# 3_mcu.net
KiCad netlist of a schematic drawn in Altium Designer
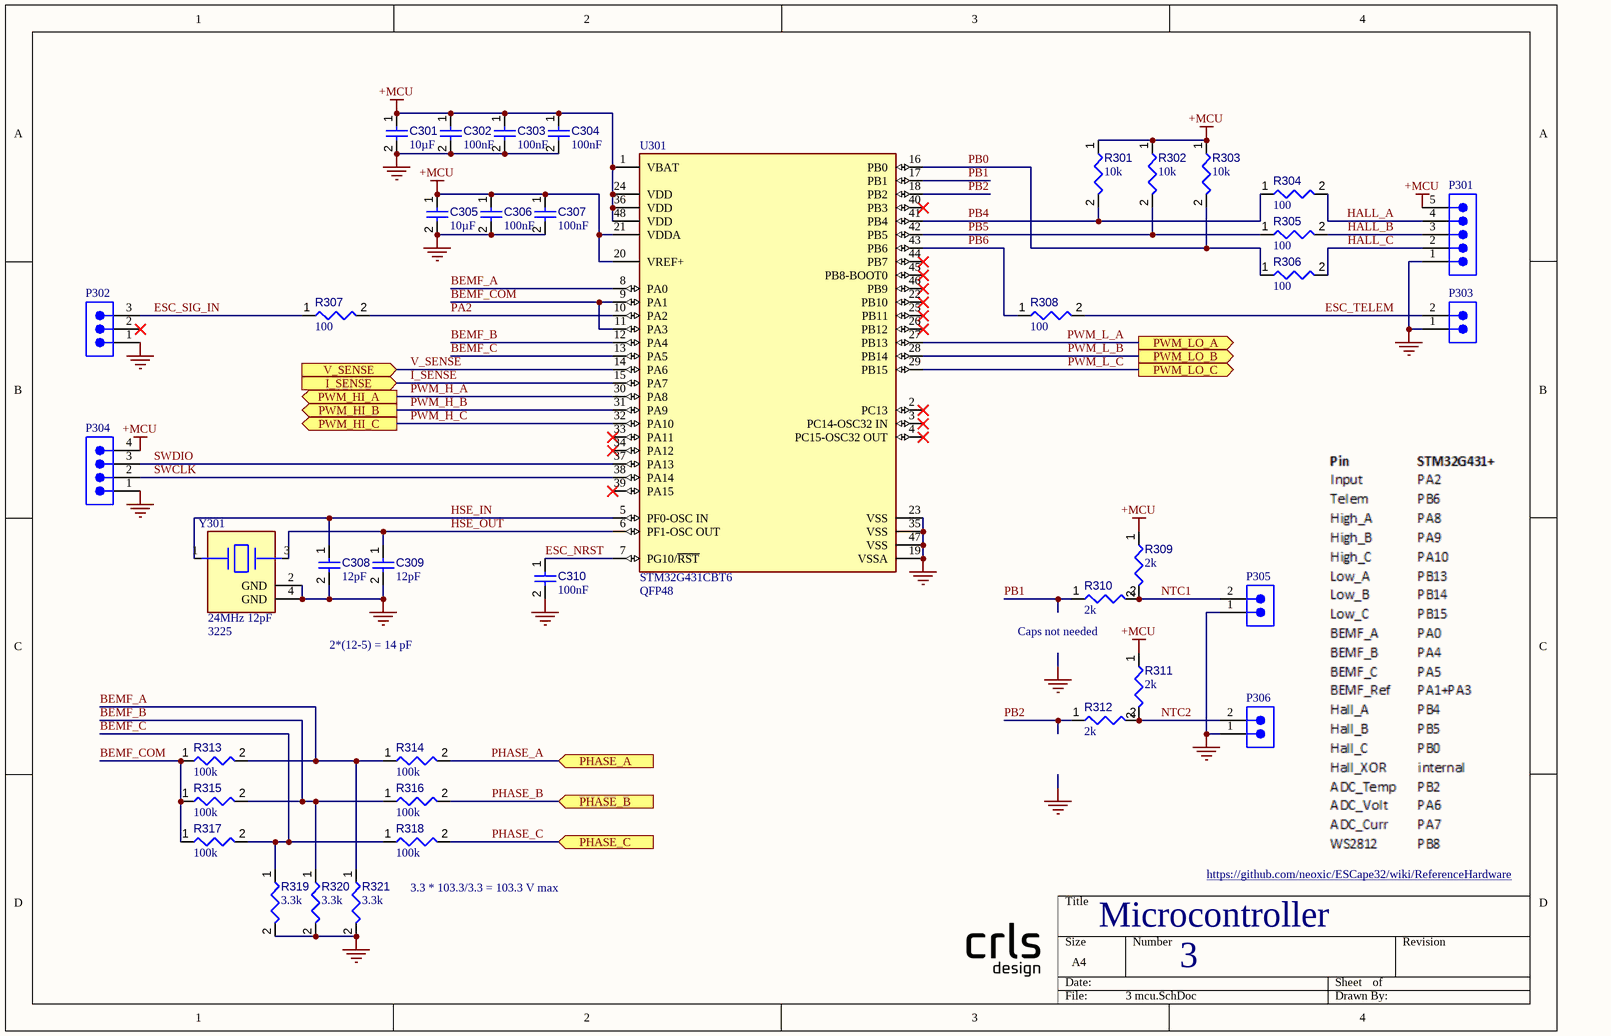
[diagram p0: 3 mcu.SchDoc]

(export (version "E")
  (design (tool "Eeschema 10.0.6"))
  (components
    (comp (ref "C301")
      (value "10µF")
      (footprint "CAPC0603(1608)100_L")
      (description "Chip Capacitor, 10µF +/-20%, 10V, 0603, Thickness 1 mm")
      (fields (field (name "TOLERANCE") "10%") (field (name "Comment") "Capacitor 10µF +/-20% 10V 0603"))
      (libsource (lib "UBC Uncrewed Aircraft Systems") (part "CAP-NP-2"))
    )
    (comp (ref "C302")
      (value "100nF")
      (footprint "CAPC0402(1005)60_L")
      (description "Chip Capacitor, 100nF +/-20%, 25V, 0402, Thickness 0.6 mm")
      (fields (field (name "TOLERANCE") "10%") (field (name "Comment") "Capacitor 100nF +/-20% 25V 0402"))
      (libsource (lib "UBC Uncrewed Aircraft Systems") (part "CAP-NP-2"))
    )
    (comp (ref "C303")
      (value "100nF")
      (footprint "CAPC0402(1005)60_L")
      (description "Chip Capacitor, 100nF +/-20%, 25V, 0402, Thickness 0.6 mm")
      (fields (field (name "TOLERANCE") "10%") (field (name "Comment") "Capacitor 100nF +/-20% 25V 0402"))
      (libsource (lib "UBC Uncrewed Aircraft Systems") (part "CAP-NP-2"))
    )
    (comp (ref "C304")
      (value "100nF")
      (footprint "CAPC0402(1005)60_L")
      (description "Chip Capacitor, 100nF +/-20%, 25V, 0402, Thickness 0.6 mm")
      (fields (field (name "TOLERANCE") "10%") (field (name "Comment") "Capacitor 100nF +/-20% 25V 0402"))
      (libsource (lib "UBC Uncrewed Aircraft Systems") (part "CAP-NP-2"))
    )
    (comp (ref "C305")
      (value "10µF")
      (footprint "CAPC0603(1608)100_L")
      (description "Chip Capacitor, 10µF +/-20%, 10V, 0603, Thickness 1 mm")
      (fields (field (name "TOLERANCE") "10%") (field (name "Comment") "Capacitor 10µF +/-20% 10V 0603"))
      (libsource (lib "UBC Uncrewed Aircraft Systems") (part "CAP-NP-2"))
    )
    (comp (ref "C306")
      (value "100nF")
      (footprint "CAPC0402(1005)60_L")
      (description "Chip Capacitor, 100nF +/-20%, 25V, 0402, Thickness 0.6 mm")
      (fields (field (name "TOLERANCE") "10%") (field (name "Comment") "Capacitor 100nF +/-20% 25V 0402"))
      (libsource (lib "UBC Uncrewed Aircraft Systems") (part "CAP-NP-2"))
    )
    (comp (ref "C307")
      (value "100nF")
      (footprint "CAPC0402(1005)60_L")
      (description "Chip Capacitor, 100nF +/-20%, 25V, 0402, Thickness 0.6 mm")
      (fields (field (name "TOLERANCE") "10%") (field (name "Comment") "Capacitor 100nF +/-20% 25V 0402"))
      (libsource (lib "UBC Uncrewed Aircraft Systems") (part "CAP-NP-2"))
    )
    (comp (ref "C308")
      (value "12pF")
      (footprint "CAPC0402(1005)33_L")
      (description "Chip Capacitor, 12pF +/-10%, 50V, 0402, Thickness 0.33 mm")
      (fields (field (name "TOLERANCE") "20%") (field (name "Comment") "Capacitor 12pF +/-10% 50V 0402"))
      (libsource (lib "UBC Uncrewed Aircraft Systems") (part "CAP-NP-2"))
    )
    (comp (ref "C309")
      (value "12pF")
      (footprint "CAPC0402(1005)33_L")
      (description "Chip Capacitor, 12pF +/-10%, 50V, 0402, Thickness 0.33 mm")
      (fields (field (name "TOLERANCE") "20%") (field (name "Comment") "Capacitor 12pF +/-10% 50V 0402"))
      (libsource (lib "UBC Uncrewed Aircraft Systems") (part "CAP-NP-2"))
    )
    (comp (ref "C310")
      (value "100nF")
      (footprint "CAPC0402(1005)60_L")
      (description "Chip Capacitor, 100nF +/-20%, 25V, 0402, Thickness 0.6 mm")
      (fields (field (name "TOLERANCE") "10%") (field (name "Comment") "Capacitor 100nF +/-20% 25V 0402"))
      (libsource (lib "UBC Uncrewed Aircraft Systems") (part "CAP-NP-2"))
    )
    (comp (ref "P301")
      (value "61300511121")
      (footprint "61300511121")
      (libsource (lib "Altium Content Vault") (part "Header_Male_1R_05P"))
    )
    (comp (ref "P302")
      (value "62000311121")
      (footprint "62000311121")
      (libsource (lib "Altium Content Vault") (part "Header_Male_1R_03P"))
    )
    (comp (ref "P303")
      (value "62000211121")
      (footprint "62000211121")
      (libsource (lib "Altium Content Vault") (part "Header_Male_1R_02P"))
    )
    (comp (ref "P304")
      (value "61300411121")
      (footprint "61300411121")
      (libsource (lib "Altium Content Vault") (part "Header_Male_1R_04P"))
    )
    (comp (ref "P305")
      (value "62000211121")
      (footprint "62000211121")
      (libsource (lib "Altium Content Vault") (part "Header_Male_1R_02P"))
    )
    (comp (ref "P306")
      (value "62000211121")
      (footprint "62000211121")
      (libsource (lib "Altium Content Vault") (part "Header_Male_1R_02P"))
    )
    (comp (ref "R301")
      (value "10k")
      (footprint "RESC0402(1005)_L")
      (description "Chip Resistor, 10 kOhms, +/-1 %, 63 mW, -55 to 125 degC, 0402")
      (fields (field (name "POWER") "63mW") (field (name "TOLERANCE") "1%"))
      (libsource (lib "UBC Uncrewed Aircraft Systems") (part "RES-2"))
    )
    (comp (ref "R302")
      (value "10k")
      (footprint "RESC0402(1005)_L")
      (description "Chip Resistor, 10 kOhms, +/-1 %, 63 mW, -55 to 125 degC, 0402")
      (fields (field (name "POWER") "63mW") (field (name "TOLERANCE") "1%"))
      (libsource (lib "UBC Uncrewed Aircraft Systems") (part "RES-2"))
    )
    (comp (ref "R303")
      (value "10k")
      (footprint "RESC0402(1005)_L")
      (description "Chip Resistor, 10 kOhms, +/-1 %, 63 mW, -55 to 125 degC, 0402")
      (fields (field (name "POWER") "63mW") (field (name "TOLERANCE") "1%"))
      (libsource (lib "UBC Uncrewed Aircraft Systems") (part "RES-2"))
    )
    (comp (ref "R304")
      (value "100")
      (footprint "RESC0402(1005)_L")
      (description "Chip Resistor, 100 Ohms, +/-1 %, 63 mW, -55 to 155 degC, 0402")
      (fields (field (name "POWER") "63mW") (field (name "TOLERANCE") "1%"))
      (libsource (lib "UBC Uncrewed Aircraft Systems") (part "RES-2"))
    )
    (comp (ref "R305")
      (value "100")
      (footprint "RESC0402(1005)_L")
      (description "Chip Resistor, 100 Ohms, +/-1 %, 63 mW, -55 to 155 degC, 0402")
      (fields (field (name "POWER") "63mW") (field (name "TOLERANCE") "1%"))
      (libsource (lib "UBC Uncrewed Aircraft Systems") (part "RES-2"))
    )
    (comp (ref "R306")
      (value "100")
      (footprint "RESC0402(1005)_L")
      (description "Chip Resistor, 100 Ohms, +/-1 %, 63 mW, -55 to 155 degC, 0402")
      (fields (field (name "POWER") "63mW") (field (name "TOLERANCE") "1%"))
      (libsource (lib "UBC Uncrewed Aircraft Systems") (part "RES-2"))
    )
    (comp (ref "R307")
      (value "100")
      (footprint "RESC0402(1005)_L")
      (description "Chip Resistor, 100 Ohms, +/-1 %, 63 mW, -55 to 155 degC, 0402")
      (fields (field (name "POWER") "63mW") (field (name "TOLERANCE") "1%"))
      (libsource (lib "UBC Uncrewed Aircraft Systems") (part "RES-2"))
    )
    (comp (ref "R308")
      (value "100")
      (footprint "RESC0402(1005)_L")
      (description "Chip Resistor, 100 Ohms, +/-1 %, 63 mW, -55 to 155 degC, 0402")
      (fields (field (name "POWER") "63mW") (field (name "TOLERANCE") "1%"))
      (libsource (lib "UBC Uncrewed Aircraft Systems") (part "RES-2"))
    )
    (comp (ref "R309")
      (value "2k")
      (footprint "RESC0402(1005)_L")
      (description "Chip Resistor, 2 kOhms, +/-5 %, 63 mW, -55 to 155 degC, 0402")
      (fields (field (name "TOLERANCE") "5%") (field (name "POWER") "63mW"))
      (libsource (lib "UBC Uncrewed Aircraft Systems") (part "RES-2"))
    )
    (comp (ref "R310")
      (value "2k")
      (footprint "RESC0402(1005)_L")
      (description "Chip Resistor, 2 kOhms, +/-5 %, 63 mW, -55 to 155 degC, 0402")
      (fields (field (name "TOLERANCE") "5%") (field (name "POWER") "63mW"))
      (libsource (lib "UBC Uncrewed Aircraft Systems") (part "RES-2"))
    )
    (comp (ref "R311")
      (value "2k")
      (footprint "RESC0402(1005)_L")
      (description "Chip Resistor, 2 kOhms, +/-5 %, 63 mW, -55 to 155 degC, 0402")
      (fields (field (name "TOLERANCE") "5%") (field (name "POWER") "63mW"))
      (libsource (lib "UBC Uncrewed Aircraft Systems") (part "RES-2"))
    )
    (comp (ref "R312")
      (value "2k")
      (footprint "RESC0402(1005)_L")
      (description "Chip Resistor, 2 kOhms, +/-5 %, 63 mW, -55 to 155 degC, 0402")
      (fields (field (name "TOLERANCE") "5%") (field (name "POWER") "63mW"))
      (libsource (lib "UBC Uncrewed Aircraft Systems") (part "RES-2"))
    )
    (comp (ref "R313")
      (value "100k")
      (footprint "RESC0402(1005)_L")
      (description "Chip Resistor, 100 kOhms, +/-1 %, 63 mW, -55 to 155 degC, 0402")
      (fields (field (name "TOLERANCE") "1%") (field (name "POWER") "63mW"))
      (libsource (lib "UBC Uncrewed Aircraft Systems") (part "RES-2"))
    )
    (comp (ref "R314")
      (value "100k")
      (footprint "RESC0402(1005)_L")
      (description "Chip Resistor, 100 kOhms, +/-1 %, 63 mW, -55 to 155 degC, 0402")
      (fields (field (name "TOLERANCE") "1%") (field (name "POWER") "63mW"))
      (libsource (lib "UBC Uncrewed Aircraft Systems") (part "RES-2"))
    )
    (comp (ref "R315")
      (value "100k")
      (footprint "RESC0402(1005)_L")
      (description "Chip Resistor, 100 kOhms, +/-1 %, 63 mW, -55 to 155 degC, 0402")
      (fields (field (name "TOLERANCE") "1%") (field (name "POWER") "63mW"))
      (libsource (lib "UBC Uncrewed Aircraft Systems") (part "RES-2"))
    )
    (comp (ref "R316")
      (value "100k")
      (footprint "RESC0402(1005)_L")
      (description "Chip Resistor, 100 kOhms, +/-1 %, 63 mW, -55 to 155 degC, 0402")
      (fields (field (name "TOLERANCE") "1%") (field (name "POWER") "63mW"))
      (libsource (lib "UBC Uncrewed Aircraft Systems") (part "RES-2"))
    )
    (comp (ref "R317")
      (value "100k")
      (footprint "RESC0402(1005)_L")
      (description "Chip Resistor, 100 kOhms, +/-1 %, 63 mW, -55 to 155 degC, 0402")
      (fields (field (name "TOLERANCE") "1%") (field (name "POWER") "63mW"))
      (libsource (lib "UBC Uncrewed Aircraft Systems") (part "RES-2"))
    )
    (comp (ref "R318")
      (value "100k")
      (footprint "RESC0402(1005)_L")
      (description "Chip Resistor, 100 kOhms, +/-1 %, 63 mW, -55 to 155 degC, 0402")
      (fields (field (name "TOLERANCE") "1%") (field (name "POWER") "63mW"))
      (libsource (lib "UBC Uncrewed Aircraft Systems") (part "RES-2"))
    )
    (comp (ref "R319")
      (value "3.3k")
      (footprint "RESC0402(1005)_L")
      (description "Chip Resistor, 3.3 kOhms, +/-1 %, 63 mW, -55 to 155 degC, 0402")
      (fields (field (name "TOLERANCE") "1%") (field (name "POWER") "63mW"))
      (libsource (lib "UBC Uncrewed Aircraft Systems") (part "RES-2"))
    )
    (comp (ref "R320")
      (value "3.3k")
      (footprint "RESC0402(1005)_L")
      (description "Chip Resistor, 3.3 kOhms, +/-1 %, 63 mW, -55 to 155 degC, 0402")
      (fields (field (name "TOLERANCE") "1%") (field (name "POWER") "63mW"))
      (libsource (lib "UBC Uncrewed Aircraft Systems") (part "RES-2"))
    )
    (comp (ref "R321")
      (value "3.3k")
      (footprint "RESC0402(1005)_L")
      (description "Chip Resistor, 3.3 kOhms, +/-1 %, 63 mW, -55 to 155 degC, 0402")
      (fields (field (name "TOLERANCE") "1%") (field (name "POWER") "63mW"))
      (libsource (lib "UBC Uncrewed Aircraft Systems") (part "RES-2"))
    )
    (comp (ref "U301")
      (value "STM32G431CBT6")
      (footprint "FP-LQFP48-5B-MFG")
      (description "MAINSTREAM ARM CORTEX-M4+ MCU 17")
      (fields
        (field (name "MANUFACTURER") "STMicroelectronics")
        (field (name "OCTOPART") "https://octopart.com/stm32g431cbt6-stmicroelectronics-98835224")
      )
      (libsource (lib "Altium Content Vault") (part "08b09c1d51ec08ade740842f2b8671b"))
    )
    (comp (ref "Y301")
      (value "TSX-3225 24.0000MF20G-AC3")
      (footprint "FP-TSX-3225-MFG")
      (description "CRYSTAL 24.0000MHZ 9PF SMD")
      (fields (field (name "TOLERANCE") "10ppm"))
      (libsource (lib "Altium Content Vault") (part "862d5228ea4a4c8f16e8fb874e464c7"))
    )
  )
  (nets
    (net (code "1") (name "+MCU") (class "Default")
      (node (ref "C301") (pin "1") (pinfunction "1_1") (pintype "passive"))
      (node (ref "C302") (pin "1") (pinfunction "1_1") (pintype "passive"))
      (node (ref "C303") (pin "1") (pinfunction "1_1") (pintype "passive"))
      (node (ref "C304") (pin "1") (pinfunction "1_1") (pintype "passive"))
      (node (ref "C305") (pin "1") (pinfunction "1_1") (pintype "passive"))
      (node (ref "C306") (pin "1") (pinfunction "1_1") (pintype "passive"))
      (node (ref "C307") (pin "1") (pinfunction "1_1") (pintype "passive"))
      (node (ref "P301") (pin "5") (pinfunction "5_5") (pintype "passive"))
      (node (ref "P304") (pin "4") (pinfunction "4_4") (pintype "passive"))
      (node (ref "R301") (pin "1") (pinfunction "1_1") (pintype "passive"))
      (node (ref "R302") (pin "1") (pinfunction "1_1") (pintype "passive"))
      (node (ref "R303") (pin "1") (pinfunction "1_1") (pintype "passive"))
      (node (ref "R309") (pin "1") (pinfunction "1_1") (pintype "passive"))
      (node (ref "R311") (pin "1") (pinfunction "1_1") (pintype "passive"))
      (node (ref "U301") (pin "1") (pinfunction "VBAT_1") (pintype "power_in"))
      (node (ref "U301") (pin "20") (pinfunction "VREF+_20") (pintype "power_in"))
      (node (ref "U301") (pin "21") (pinfunction "VDDA_21") (pintype "power_in"))
      (node (ref "U301") (pin "24") (pinfunction "VDD_24") (pintype "power_in"))
      (node (ref "U301") (pin "36") (pinfunction "VDD_36") (pintype "power_in"))
      (node (ref "U301") (pin "48") (pinfunction "VDD_48") (pintype "power_in"))
    )
    (net (code "2") (name "/BEMF_A") (class "Default")
      (node (ref "R313") (pin "2") (pinfunction "2_2") (pintype "passive"))
      (node (ref "R314") (pin "1") (pinfunction "1_1") (pintype "passive"))
      (node (ref "R321") (pin "1") (pinfunction "1_1") (pintype "passive"))
      (node (ref "U301") (pin "8") (pinfunction "PA0_8") (pintype "bidirectional"))
    )
    (net (code "3") (name "/BEMF_B") (class "Default")
      (node (ref "R315") (pin "2") (pinfunction "2_2") (pintype "passive"))
      (node (ref "R316") (pin "1") (pinfunction "1_1") (pintype "passive"))
      (node (ref "R320") (pin "1") (pinfunction "1_1") (pintype "passive"))
      (node (ref "U301") (pin "12") (pinfunction "PA4_12") (pintype "bidirectional"))
    )
    (net (code "4") (name "/BEMF_C") (class "Default")
      (node (ref "R317") (pin "2") (pinfunction "2_2") (pintype "passive"))
      (node (ref "R318") (pin "1") (pinfunction "1_1") (pintype "passive"))
      (node (ref "R319") (pin "1") (pinfunction "1_1") (pintype "passive"))
      (node (ref "U301") (pin "13") (pinfunction "PA5_13") (pintype "bidirectional"))
    )
    (net (code "5") (name "/BEMF_COM") (class "Default")
      (node (ref "R313") (pin "1") (pinfunction "1_1") (pintype "passive"))
      (node (ref "R315") (pin "1") (pinfunction "1_1") (pintype "passive"))
      (node (ref "R317") (pin "1") (pinfunction "1_1") (pintype "passive"))
      (node (ref "U301") (pin "11") (pinfunction "PA3_11") (pintype "bidirectional"))
      (node (ref "U301") (pin "9") (pinfunction "PA1_9") (pintype "bidirectional"))
    )
    (net (code "6") (name "/ESC_NRST") (class "Default")
      (node (ref "C310") (pin "1") (pinfunction "1_1") (pintype "passive"))
      (node (ref "U301") (pin "7") (pinfunction "PG10/~{RST}_7") (pintype "bidirectional"))
    )
    (net (code "7") (name "/ESC_SIG_IN") (class "Default")
      (node (ref "P302") (pin "3") (pinfunction "3_3") (pintype "passive"))
      (node (ref "R307") (pin "1") (pinfunction "1_1") (pintype "passive"))
    )
    (net (code "8") (name "/ESC_TELEM") (class "Default")
      (node (ref "P303") (pin "2") (pinfunction "2_2") (pintype "passive"))
      (node (ref "R308") (pin "2") (pinfunction "2_2") (pintype "passive"))
    )
    (net (code "9") (name "/HALL_A") (class "Default")
      (node (ref "P301") (pin "4") (pinfunction "4_4") (pintype "passive"))
      (node (ref "R304") (pin "2") (pinfunction "2_2") (pintype "passive"))
    )
    (net (code "10") (name "/HALL_B") (class "Default")
      (node (ref "P301") (pin "3") (pinfunction "3_3") (pintype "passive"))
      (node (ref "R305") (pin "2") (pinfunction "2_2") (pintype "passive"))
    )
    (net (code "11") (name "/HALL_C") (class "Default")
      (node (ref "P301") (pin "2") (pinfunction "2_2") (pintype "passive"))
      (node (ref "R306") (pin "2") (pinfunction "2_2") (pintype "passive"))
    )
    (net (code "12") (name "/HSE_IN") (class "Default")
      (node (ref "C308") (pin "1") (pinfunction "1_1") (pintype "passive"))
      (node (ref "U301") (pin "5") (pinfunction "PF0-OSC_IN_5") (pintype "bidirectional"))
      (node (ref "Y301") (pin "1") (pinfunction "1_1") (pintype "passive"))
    )
    (net (code "13") (name "/HSE_OUT") (class "Default")
      (node (ref "C309") (pin "1") (pinfunction "1_1") (pintype "passive"))
      (node (ref "U301") (pin "6") (pinfunction "PF1-OSC_OUT_6") (pintype "bidirectional"))
      (node (ref "Y301") (pin "3") (pinfunction "3_3") (pintype "passive"))
    )
    (net (code "14") (name "/I_SENSE") (class "Default")
      (node (ref "U301") (pin "15") (pinfunction "PA7_15") (pintype "bidirectional"))
    )
    (net (code "15") (name "/NTC1") (class "Default")
      (node (ref "P305") (pin "2") (pinfunction "2_2") (pintype "passive"))
      (node (ref "R309") (pin "2") (pinfunction "2_2") (pintype "passive"))
      (node (ref "R310") (pin "2") (pinfunction "2_2") (pintype "passive"))
    )
    (net (code "16") (name "/NTC2") (class "Default")
      (node (ref "P306") (pin "2") (pinfunction "2_2") (pintype "passive"))
      (node (ref "R311") (pin "2") (pinfunction "2_2") (pintype "passive"))
      (node (ref "R312") (pin "2") (pinfunction "2_2") (pintype "passive"))
    )
    (net (code "17") (name "/PA2") (class "Default")
      (node (ref "R307") (pin "2") (pinfunction "2_2") (pintype "passive"))
      (node (ref "U301") (pin "10") (pinfunction "PA2_10") (pintype "bidirectional"))
    )
    (net (code "18") (name "/PB0") (class "Default")
      (node (ref "R303") (pin "2") (pinfunction "2_2") (pintype "passive"))
      (node (ref "R306") (pin "1") (pinfunction "1_1") (pintype "passive"))
      (node (ref "U301") (pin "16") (pinfunction "PB0_16") (pintype "bidirectional"))
    )
    (net (code "19") (name "/PB1") (class "Default")
      (node (ref "R310") (pin "1") (pinfunction "1_1") (pintype "passive"))
      (node (ref "U301") (pin "17") (pinfunction "PB1_17") (pintype "bidirectional"))
    )
    (net (code "20") (name "/PB2") (class "Default")
      (node (ref "R312") (pin "1") (pinfunction "1_1") (pintype "passive"))
      (node (ref "U301") (pin "18") (pinfunction "PB2_18") (pintype "bidirectional"))
    )
    (net (code "21") (name "/PB4") (class "Default")
      (node (ref "R301") (pin "2") (pinfunction "2_2") (pintype "passive"))
      (node (ref "R304") (pin "1") (pinfunction "1_1") (pintype "passive"))
      (node (ref "U301") (pin "41") (pinfunction "PB4_41") (pintype "bidirectional"))
    )
    (net (code "22") (name "/PB5") (class "Default")
      (node (ref "R302") (pin "2") (pinfunction "2_2") (pintype "passive"))
      (node (ref "R305") (pin "1") (pinfunction "1_1") (pintype "passive"))
      (node (ref "U301") (pin "42") (pinfunction "PB5_42") (pintype "bidirectional"))
    )
    (net (code "23") (name "/PB6") (class "Default")
      (node (ref "R308") (pin "1") (pinfunction "1_1") (pintype "passive"))
      (node (ref "U301") (pin "43") (pinfunction "PB6_43") (pintype "bidirectional"))
    )
    (net (code "24") (name "/PHASE_A") (class "Default")
      (node (ref "R314") (pin "2") (pinfunction "2_2") (pintype "passive"))
    )
    (net (code "25") (name "/PHASE_B") (class "Default")
      (node (ref "R316") (pin "2") (pinfunction "2_2") (pintype "passive"))
    )
    (net (code "26") (name "/PHASE_C") (class "Default")
      (node (ref "R318") (pin "2") (pinfunction "2_2") (pintype "passive"))
    )
    (net (code "27") (name "/PWM_H_A") (class "Default")
      (node (ref "U301") (pin "30") (pinfunction "PA8_30") (pintype "bidirectional"))
    )
    (net (code "28") (name "/PWM_H_B") (class "Default")
      (node (ref "U301") (pin "31") (pinfunction "PA9_31") (pintype "bidirectional"))
    )
    (net (code "29") (name "/PWM_H_C") (class "Default")
      (node (ref "U301") (pin "32") (pinfunction "PA10_32") (pintype "bidirectional"))
    )
    (net (code "30") (name "/PWM_L_A") (class "Default")
      (node (ref "U301") (pin "27") (pinfunction "PB13_27") (pintype "bidirectional"))
    )
    (net (code "31") (name "/PWM_L_B") (class "Default")
      (node (ref "U301") (pin "28") (pinfunction "PB14_28") (pintype "bidirectional"))
    )
    (net (code "32") (name "/PWM_L_C") (class "Default")
      (node (ref "U301") (pin "29") (pinfunction "PB15_29") (pintype "bidirectional"))
    )
    (net (code "33") (name "/SWCLK") (class "Default")
      (node (ref "P304") (pin "2") (pinfunction "2_2") (pintype "passive"))
      (node (ref "U301") (pin "38") (pinfunction "PA14_38") (pintype "bidirectional"))
    )
    (net (code "34") (name "/SWDIO") (class "Default")
      (node (ref "P304") (pin "3") (pinfunction "3_3") (pintype "passive"))
      (node (ref "U301") (pin "37") (pinfunction "PA13_37") (pintype "bidirectional"))
    )
    (net (code "35") (name "/V_SENSE") (class "Default")
      (node (ref "U301") (pin "14") (pinfunction "PA6_14") (pintype "bidirectional"))
    )
    (net (code "36") (name "GND") (class "Default")
      (node (ref "C301") (pin "2") (pinfunction "2_2") (pintype "passive"))
      (node (ref "C302") (pin "2") (pinfunction "2_2") (pintype "passive"))
      (node (ref "C303") (pin "2") (pinfunction "2_2") (pintype "passive"))
      (node (ref "C304") (pin "2") (pinfunction "2_2") (pintype "passive"))
      (node (ref "C305") (pin "2") (pinfunction "2_2") (pintype "passive"))
      (node (ref "C306") (pin "2") (pinfunction "2_2") (pintype "passive"))
      (node (ref "C307") (pin "2") (pinfunction "2_2") (pintype "passive"))
      (node (ref "C308") (pin "2") (pinfunction "2_2") (pintype "passive"))
      (node (ref "C309") (pin "2") (pinfunction "2_2") (pintype "passive"))
      (node (ref "C310") (pin "2") (pinfunction "2_2") (pintype "passive"))
      (node (ref "P301") (pin "1") (pinfunction "1_1") (pintype "passive"))
      (node (ref "P302") (pin "1") (pinfunction "1_1") (pintype "passive"))
      (node (ref "P303") (pin "1") (pinfunction "1_1") (pintype "passive"))
      (node (ref "P304") (pin "1") (pinfunction "1_1") (pintype "passive"))
      (node (ref "P305") (pin "1") (pinfunction "1_1") (pintype "passive"))
      (node (ref "P306") (pin "1") (pinfunction "1_1") (pintype "passive"))
      (node (ref "R319") (pin "2") (pinfunction "2_2") (pintype "passive"))
      (node (ref "R320") (pin "2") (pinfunction "2_2") (pintype "passive"))
      (node (ref "R321") (pin "2") (pinfunction "2_2") (pintype "passive"))
      (node (ref "U301") (pin "19") (pinfunction "VSSA_19") (pintype "power_in"))
      (node (ref "U301") (pin "23") (pinfunction "VSS_23") (pintype "power_in"))
      (node (ref "U301") (pin "35") (pinfunction "VSS_35") (pintype "power_in"))
      (node (ref "U301") (pin "47") (pinfunction "VSS_47") (pintype "power_in"))
      (node (ref "Y301") (pin "2") (pinfunction "GND_2") (pintype "power_in"))
      (node (ref "Y301") (pin "4") (pinfunction "GND_4") (pintype "power_in"))
    )
    (net (code "37") (name "unconnected-(P302-Pad2)") (class "Default")
      (node (ref "P302") (pin "2") (pinfunction "2_2") (pintype "passive+no_connect"))
    )
    (net (code "38") (name "unconnected-(U301-PA11-Pad33)") (class "Default")
      (node (ref "U301") (pin "33") (pinfunction "PA11_33") (pintype "bidirectional+no_connect"))
    )
    (net (code "39") (name "unconnected-(U301-PA12-Pad34)") (class "Default")
      (node (ref "U301") (pin "34") (pinfunction "PA12_34") (pintype "bidirectional+no_connect"))
    )
    (net (code "40") (name "unconnected-(U301-PA15-Pad39)") (class "Default")
      (node (ref "U301") (pin "39") (pinfunction "PA15_39") (pintype "bidirectional+no_connect"))
    )
    (net (code "41") (name "unconnected-(U301-PB3-Pad40)") (class "Default")
      (node (ref "U301") (pin "40") (pinfunction "PB3_40") (pintype "bidirectional+no_connect"))
    )
    (net (code "42") (name "unconnected-(U301-PB7-Pad44)") (class "Default")
      (node (ref "U301") (pin "44") (pinfunction "PB7_44") (pintype "bidirectional+no_connect"))
    )
    (net (code "43") (name "unconnected-(U301-PB8-BOOT0-Pad45)") (class "Default")
      (node (ref "U301") (pin "45") (pinfunction "PB8-BOOT0_45") (pintype "bidirectional+no_connect"))
    )
    (net (code "44") (name "unconnected-(U301-PB9-Pad46)") (class "Default")
      (node (ref "U301") (pin "46") (pinfunction "PB9_46") (pintype "bidirectional+no_connect"))
    )
    (net (code "45") (name "unconnected-(U301-PB10-Pad22)") (class "Default")
      (node (ref "U301") (pin "22") (pinfunction "PB10_22") (pintype "bidirectional+no_connect"))
    )
    (net (code "46") (name "unconnected-(U301-PB11-Pad25)") (class "Default")
      (node (ref "U301") (pin "25") (pinfunction "PB11_25") (pintype "bidirectional+no_connect"))
    )
    (net (code "47") (name "unconnected-(U301-PB12-Pad26)") (class "Default")
      (node (ref "U301") (pin "26") (pinfunction "PB12_26") (pintype "bidirectional+no_connect"))
    )
    (net (code "48") (name "unconnected-(U301-PC13-Pad2)") (class "Default")
      (node (ref "U301") (pin "2") (pinfunction "PC13_2") (pintype "bidirectional+no_connect"))
    )
    (net (code "49") (name "unconnected-(U301-PC14-OSC32_IN-Pad3)") (class "Default")
      (node (ref "U301") (pin "3") (pinfunction "PC14-OSC32_IN_3") (pintype "bidirectional+no_connect"))
    )
    (net (code "50") (name "unconnected-(U301-PC15-OSC32_OUT-Pad4)") (class "Default")
      (node (ref "U301") (pin "4") (pinfunction "PC15-OSC32_OUT_4") (pintype "bidirectional+no_connect"))
    )
  )
)
